# CAN.net
KiCad netlist of a schematic drawn in Altium Designer
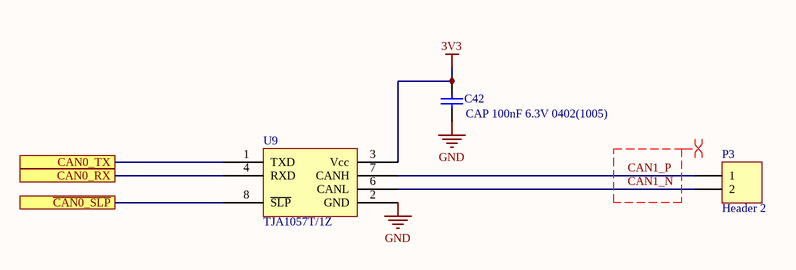
[diagram p0: CAN.SchDoc]

(export (version "E")
  (design (tool "Eeschema 10.0.6"))
  (components
    (comp (ref "C42")
      (value "CAP 100nF 6.3V 0402(1005)")
      (footprint "CAPC0402(1005)60_M")
      (description "CAP 100nF 6.3V ±20% 0402 (1005 Metric) Thickness 0.6mm SMD")
      (fields (field (name "TOLERANCE") "Â±20%"))
      (libsource (lib "Altium Content Vault") (part "CAP"))
    )
    (comp (ref "P3")
      (value "Header 2")
      (footprint "HDR1X2")
      (description "Header, 2-Pin")
      (fields (field (name "PUBLISHER") "Altium Limited"))
      (libsource (lib "Parts") (part "Header 2"))
    )
    (comp (ref "U9")
      (value "TJA1057T/1Z")
      (footprint "SOIC127P600X175-8N")
      (description "CAN-FD XVR 5v")
      (libsource (lib "parts") (part "TJA1057T/1Z"))
    )
  )
  (nets
    (net (code "1") (name "/CAN0_RX") (class "Default")
      (node (ref "U9") (pin "4") (pinfunction "RXD_4") (pintype "passive"))
    )
    (net (code "2") (name "/CAN0_SLP") (class "Default")
      (node (ref "U9") (pin "8") (pinfunction "SLP_8") (pintype "passive"))
    )
    (net (code "3") (name "/CAN0_TX") (class "Default")
      (node (ref "U9") (pin "1") (pinfunction "TXD_1") (pintype "passive"))
    )
    (net (code "4") (name "/CAN1_N") (class "Default")
      (node (ref "P3") (pin "2") (pinfunction "2_2") (pintype "passive"))
      (node (ref "U9") (pin "6") (pinfunction "CANL_6") (pintype "passive"))
    )
    (net (code "5") (name "/CAN1_P") (class "Default")
      (node (ref "P3") (pin "1") (pinfunction "1_1") (pintype "passive"))
      (node (ref "U9") (pin "7") (pinfunction "CANH_7") (pintype "passive"))
    )
    (net (code "6") (name "3V3") (class "Default")
      (node (ref "C42") (pin "2") (pinfunction "2_2") (pintype "passive"))
      (node (ref "U9") (pin "3") (pinfunction "Vcc_3") (pintype "passive"))
    )
    (net (code "7") (name "GND") (class "Default")
      (node (ref "C42") (pin "1") (pinfunction "1_1") (pintype "passive"))
      (node (ref "U9") (pin "2") (pinfunction "GND_2") (pintype "passive"))
    )
  )
)
